# 9_-CAMERA_POWER_CONTROLLER.net
KiCad netlist of a schematic drawn in Altium Designer
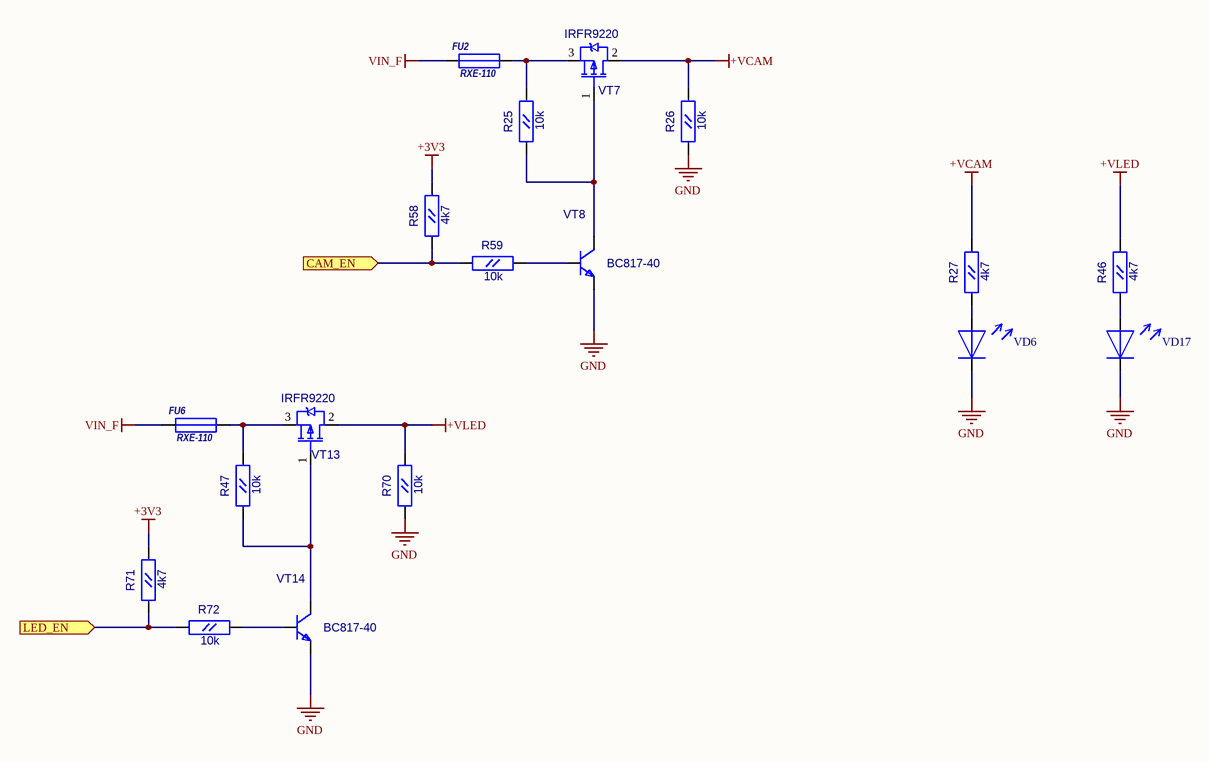
[diagram p0: [9]-CAMERA_POWER_CONTROLLER.SchDoc]

(export (version "E")
  (design (tool "Eeschema 10.0.6"))
  (components
    (comp (ref "FU2") (value "RXE-110") (footprint "RXE-110") (libsource (lib "fizik_lib") (part "RXE-110")))
    (comp (ref "FU6") (value "RXE-110") (footprint "RXE-110") (libsource (lib "fizik_lib") (part "RXE-110")))
    (comp (ref "R25")
      (value "10k")
      (footprint "RC0603")
      (description "RC0603")
      (libsource (lib "fizik_lib") (part "RC0603"))
    )
    (comp (ref "R26")
      (value "10k")
      (footprint "RC0603")
      (description "RC0603")
      (libsource (lib "fizik_lib") (part "RC0603"))
    )
    (comp (ref "R27")
      (value "4k7")
      (footprint "RC0603")
      (description "RC0603")
      (libsource (lib "gprs_modem_2") (part "RC0603"))
    )
    (comp (ref "R46")
      (value "4k7")
      (footprint "RC0603")
      (description "RC0603")
      (libsource (lib "gprs_modem_2") (part "RC0603"))
    )
    (comp (ref "R47")
      (value "10k")
      (footprint "RC0603")
      (description "RC0603")
      (libsource (lib "fizik_lib") (part "RC0603"))
    )
    (comp (ref "R58")
      (value "4k7")
      (footprint "RC0603")
      (description "RC0603")
      (libsource (lib "fizik_lib") (part "RC0603"))
    )
    (comp (ref "R59")
      (value "10k")
      (footprint "RC0603")
      (description "RC0603")
      (libsource (lib "fizik_lib") (part "RC0603"))
    )
    (comp (ref "R70")
      (value "10k")
      (footprint "RC0603")
      (description "RC0603")
      (libsource (lib "fizik_lib") (part "RC0603"))
    )
    (comp (ref "R71")
      (value "4k7")
      (footprint "RC0603")
      (description "RC0603")
      (libsource (lib "fizik_lib") (part "RC0603"))
    )
    (comp (ref "R72")
      (value "10k")
      (footprint "RC0603")
      (description "RC0603")
      (libsource (lib "fizik_lib") (part "RC0603"))
    )
    (comp (ref "VD6")
      (value "LED_0805")
      (footprint "LED0805")
      (libsource (lib "gprs_modem_2") (part "LED_0805"))
    )
    (comp (ref "VD17")
      (value "LED_0805")
      (footprint "LED0805")
      (libsource (lib "gprs_modem_2") (part "LED_0805"))
    )
    (comp (ref "VT7")
      (value "IRFR9220")
      (footprint "D-PAK(TO-252AA)")
      (description "HEXFET Power MOSFET")
      (libsource (lib "gprs_modem_2") (part "IRFR9220"))
    )
    (comp (ref "VT8")
      (value "BC817-40")
      (footprint "SOT-23(123)")
      (description "NPN 500ma transistor")
      (libsource (lib "fizik_lib") (part "BC846BLT1"))
    )
    (comp (ref "VT13")
      (value "IRFR9220")
      (footprint "D-PAK(TO-252AA)")
      (description "HEXFET Power MOSFET")
      (libsource (lib "gprs_modem_2") (part "IRFR9220"))
    )
    (comp (ref "VT14")
      (value "BC817-40")
      (footprint "SOT-23(123)")
      (description "NPN 500ma transistor")
      (libsource (lib "fizik_lib") (part "BC846BLT1"))
    )
  )
  (nets
    (net (code "1") (name "+3V3") (class "Default")
      (node (ref "R58") (pin "2") (pinfunction "B_2") (pintype "passive"))
      (node (ref "R71") (pin "2") (pinfunction "B_2") (pintype "passive"))
    )
    (net (code "2") (name "+VCAM") (class "Default")
      (node (ref "R26") (pin "2") (pinfunction "B_2") (pintype "passive"))
      (node (ref "R27") (pin "2") (pinfunction "B_2") (pintype "passive"))
      (node (ref "VT7") (pin "2") (pinfunction "D_2") (pintype "passive"))
    )
    (net (code "3") (name "+VLED") (class "Default")
      (node (ref "R46") (pin "2") (pinfunction "B_2") (pintype "passive"))
      (node (ref "R70") (pin "2") (pinfunction "B_2") (pintype "passive"))
      (node (ref "VT13") (pin "2") (pinfunction "D_2") (pintype "passive"))
    )
    (net (code "4") (name "/CAM_EN") (class "Default")
      (node (ref "R58") (pin "1") (pinfunction "A_1") (pintype "passive"))
      (node (ref "R59") (pin "1") (pinfunction "A_1") (pintype "passive"))
    )
    (net (code "5") (name "/LED_EN") (class "Default")
      (node (ref "R71") (pin "1") (pinfunction "A_1") (pintype "passive"))
      (node (ref "R72") (pin "1") (pinfunction "A_1") (pintype "passive"))
    )
    (net (code "6") (name "GND") (class "Default")
      (node (ref "R26") (pin "1") (pinfunction "A_1") (pintype "passive"))
      (node (ref "R70") (pin "1") (pinfunction "A_1") (pintype "passive"))
      (node (ref "VD17") (pin "2") (pintype "passive"))
      (node (ref "VD6") (pin "2") (pintype "passive"))
      (node (ref "VT14") (pin "2") (pinfunction "E_2") (pintype "passive"))
      (node (ref "VT8") (pin "2") (pinfunction "E_2") (pintype "passive"))
    )
    (net (code "7") (name "Net-(R25-A)") (class "Default")
      (node (ref "R25") (pin "1") (pinfunction "A_1") (pintype "passive"))
      (node (ref "VT7") (pin "1") (pinfunction "G_1") (pintype "passive"))
      (node (ref "VT8") (pin "3") (pinfunction "C_3") (pintype "passive"))
    )
    (net (code "8") (name "Net-(R25-B)") (class "Default")
      (node (ref "FU2") (pin "2") (pintype "passive"))
      (node (ref "R25") (pin "2") (pinfunction "B_2") (pintype "passive"))
      (node (ref "VT7") (pin "3") (pinfunction "S_3") (pintype "passive"))
    )
    (net (code "9") (name "Net-(R27-A)") (class "Default")
      (node (ref "R27") (pin "1") (pinfunction "A_1") (pintype "passive"))
      (node (ref "VD6") (pin "1") (pintype "passive"))
    )
    (net (code "10") (name "Net-(R46-A)") (class "Default")
      (node (ref "R46") (pin "1") (pinfunction "A_1") (pintype "passive"))
      (node (ref "VD17") (pin "1") (pintype "passive"))
    )
    (net (code "11") (name "Net-(R47-A)") (class "Default")
      (node (ref "R47") (pin "1") (pinfunction "A_1") (pintype "passive"))
      (node (ref "VT13") (pin "1") (pinfunction "G_1") (pintype "passive"))
      (node (ref "VT14") (pin "3") (pinfunction "C_3") (pintype "passive"))
    )
    (net (code "12") (name "Net-(R47-B)") (class "Default")
      (node (ref "FU6") (pin "2") (pintype "passive"))
      (node (ref "R47") (pin "2") (pinfunction "B_2") (pintype "passive"))
      (node (ref "VT13") (pin "3") (pinfunction "S_3") (pintype "passive"))
    )
    (net (code "13") (name "Net-(R59-B)") (class "Default")
      (node (ref "R59") (pin "2") (pinfunction "B_2") (pintype "passive"))
      (node (ref "VT8") (pin "1") (pinfunction "B_1") (pintype "passive"))
    )
    (net (code "14") (name "Net-(R72-B)") (class "Default")
      (node (ref "R72") (pin "2") (pinfunction "B_2") (pintype "passive"))
      (node (ref "VT14") (pin "1") (pinfunction "B_1") (pintype "passive"))
    )
    (net (code "15") (name "VIN_F") (class "Default")
      (node (ref "FU2") (pin "1") (pintype "passive"))
      (node (ref "FU6") (pin "1") (pintype "passive"))
    )
  )
)
